# power.net
KiCad netlist of a schematic drawn in Altium Designer
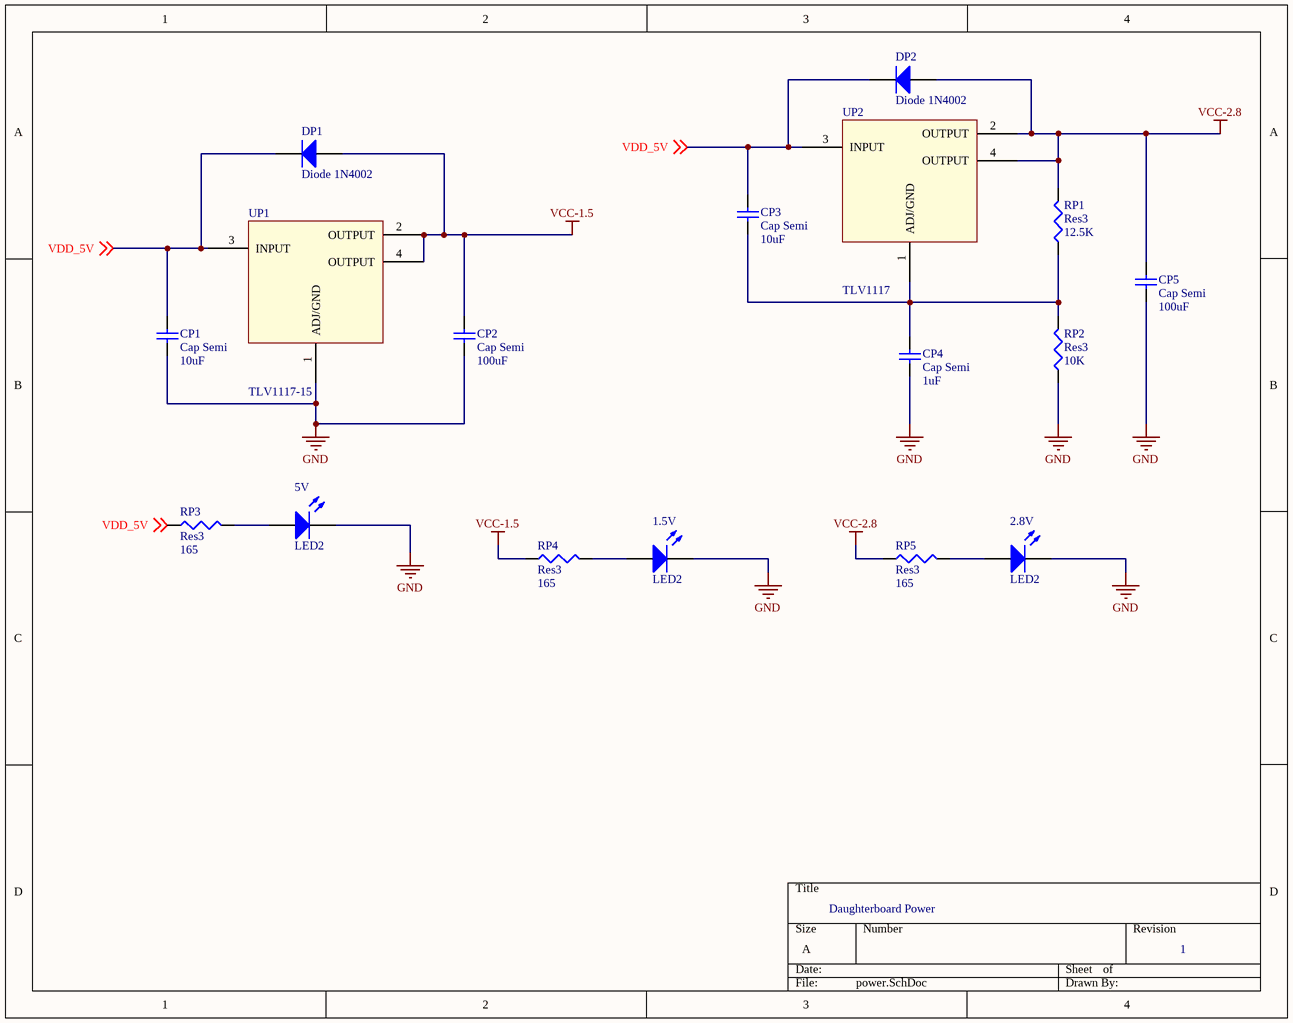
[diagram p0: power.SchDoc]

(export (version "E")
  (design (tool "Eeschema 10.0.6"))
  (components
    (comp (ref "1.5V")
      (value "LED2")
      (footprint "DIODE1608")
      (description "Typical RED, GREEN, YELLOW, AMBER GaAs LED")
      (fields (field (name "PUBLISHER") "Altium Limited"))
      (libsource (lib "Miscellaneous Devices") (part "LED2"))
    )
    (comp (ref "2.8V")
      (value "LED2")
      (footprint "DIODE1608")
      (description "Typical RED, GREEN, YELLOW, AMBER GaAs LED")
      (fields (field (name "PUBLISHER") "Altium Limited"))
      (libsource (lib "Miscellaneous Devices") (part "LED2"))
    )
    (comp (ref "5V")
      (value "LED2")
      (footprint "DIODE1608")
      (description "Typical RED, GREEN, YELLOW, AMBER GaAs LED")
      (fields (field (name "PUBLISHER") "Altium Limited"))
      (libsource (lib "Miscellaneous Devices") (part "LED2"))
    )
    (comp (ref "CP1")
      (value "Cap Semi")
      (footprint "CAPC1608L")
      (description "Capacitor (Semiconductor SIM Model)")
      (fields (field (name "ALTIUM_VALUE") "10uF") (field (name "PUBLISHER") "Altium Limited"))
      (libsource (lib "Miscellaneous Devices") (part "Cap Semi"))
    )
    (comp (ref "CP2")
      (value "Cap Semi")
      (footprint "CAPC1608L")
      (description "Capacitor (Semiconductor SIM Model)")
      (fields (field (name "ALTIUM_VALUE") "100uF") (field (name "PUBLISHER") "Altium Limited"))
      (libsource (lib "Miscellaneous Devices") (part "Cap Semi"))
    )
    (comp (ref "CP3")
      (value "Cap Semi")
      (footprint "CAPC1608L")
      (description "Capacitor (Semiconductor SIM Model)")
      (fields (field (name "ALTIUM_VALUE") "10uF") (field (name "PUBLISHER") "Altium Limited"))
      (libsource (lib "Miscellaneous Devices") (part "Cap Semi"))
    )
    (comp (ref "CP4")
      (value "Cap Semi")
      (footprint "CAPC1608L")
      (description "Capacitor (Semiconductor SIM Model)")
      (fields (field (name "ALTIUM_VALUE") "1uF") (field (name "PUBLISHER") "Altium Limited"))
      (libsource (lib "Miscellaneous Devices") (part "Cap Semi"))
    )
    (comp (ref "CP5")
      (value "Cap Semi")
      (footprint "CAPC1608L")
      (description "Capacitor (Semiconductor SIM Model)")
      (fields (field (name "ALTIUM_VALUE") "100uF") (field (name "PUBLISHER") "Altium Limited"))
      (libsource (lib "Miscellaneous Devices") (part "Cap Semi"))
    )
    (comp (ref "DP1")
      (value "Diode 1N4002")
      (footprint "DIO10.46-5.3x2.8")
      (description "1 Amp General Purpose Rectifier")
      (fields (field (name "PUBLISHER") "Altium Limited"))
      (libsource (lib "Miscellaneous Devices") (part "Diode 1N4002"))
    )
    (comp (ref "DP2")
      (value "Diode 1N4002")
      (footprint "DIO10.46-5.3x2.8")
      (description "1 Amp General Purpose Rectifier")
      (fields (field (name "PUBLISHER") "Altium Limited"))
      (libsource (lib "Miscellaneous Devices") (part "Diode 1N4002"))
    )
    (comp (ref "RP1")
      (value "Res3")
      (footprint "RESC1608L")
      (description "Resistor")
      (fields (field (name "ALTIUM_VALUE") "12.5K") (field (name "PUBLISHER") "Altium Limited"))
      (libsource (lib "Miscellaneous Devices") (part "Res3"))
    )
    (comp (ref "RP2")
      (value "Res3")
      (footprint "RESC1608L")
      (description "Resistor")
      (fields (field (name "ALTIUM_VALUE") "10K") (field (name "PUBLISHER") "Altium Limited"))
      (libsource (lib "Miscellaneous Devices") (part "Res3"))
    )
    (comp (ref "RP3")
      (value "Res3")
      (footprint "RESC1608L")
      (description "Resistor")
      (fields (field (name "ALTIUM_VALUE") "165") (field (name "PUBLISHER") "Altium Limited"))
      (libsource (lib "Miscellaneous Devices") (part "Res3"))
    )
    (comp (ref "RP4")
      (value "Res3")
      (footprint "RESC1608L")
      (description "Resistor")
      (fields (field (name "ALTIUM_VALUE") "165") (field (name "PUBLISHER") "Altium Limited"))
      (libsource (lib "Miscellaneous Devices") (part "Res3"))
    )
    (comp (ref "RP5")
      (value "Res3")
      (footprint "RESC1608L")
      (description "Resistor")
      (fields (field (name "ALTIUM_VALUE") "165") (field (name "PUBLISHER") "Altium Limited"))
      (libsource (lib "Miscellaneous Devices") (part "Res3"))
    )
    (comp (ref "UP1")
      (value "TLV1117-15")
      (footprint "TLV1117-DCY")
      (libsource (lib "daughterboard") (part "TLV1117"))
    )
    (comp (ref "UP2")
      (value "TLV1117")
      (footprint "TLV1117-DCY")
      (libsource (lib "daughterboard") (part "TLV1117"))
    )
  )
  (nets
    (net (code "1") (name "GND") (class "Default")
      (node (ref "1.5V") (pin "2") (pinfunction "K_2") (pintype "passive"))
      (node (ref "2.8V") (pin "2") (pinfunction "K_2") (pintype "passive"))
      (node (ref "5V") (pin "2") (pinfunction "K_2") (pintype "passive"))
      (node (ref "CP1") (pin "1") (pinfunction "1_1") (pintype "passive"))
      (node (ref "CP2") (pin "1") (pinfunction "1_1") (pintype "passive"))
      (node (ref "CP4") (pin "1") (pinfunction "1_1") (pintype "passive"))
      (node (ref "CP5") (pin "1") (pinfunction "1_1") (pintype "passive"))
      (node (ref "RP2") (pin "1") (pinfunction "1_1") (pintype "passive"))
      (node (ref "UP1") (pin "1") (pinfunction "ADJ/GND_1") (pintype "passive"))
    )
    (net (code "2") (name "Net-(1.5V-A)") (class "Default")
      (node (ref "1.5V") (pin "1") (pinfunction "A_1") (pintype "passive"))
      (node (ref "RP4") (pin "2") (pinfunction "2_2") (pintype "passive"))
    )
    (net (code "3") (name "Net-(2.8V-A)") (class "Default")
      (node (ref "2.8V") (pin "1") (pinfunction "A_1") (pintype "passive"))
      (node (ref "RP5") (pin "2") (pinfunction "2_2") (pintype "passive"))
    )
    (net (code "4") (name "Net-(5V-A)") (class "Default")
      (node (ref "5V") (pin "1") (pinfunction "A_1") (pintype "passive"))
      (node (ref "RP3") (pin "2") (pinfunction "2_2") (pintype "passive"))
    )
    (net (code "5") (name "Net-(UP2-ADJ{slash}GND)") (class "Default")
      (node (ref "CP3") (pin "1") (pinfunction "1_1") (pintype "passive"))
      (node (ref "CP4") (pin "2") (pinfunction "2_2") (pintype "passive"))
      (node (ref "RP1") (pin "1") (pinfunction "1_1") (pintype "passive"))
      (node (ref "RP2") (pin "2") (pinfunction "2_2") (pintype "passive"))
      (node (ref "UP2") (pin "1") (pinfunction "ADJ/GND_1") (pintype "passive"))
    )
    (net (code "6") (name "VCC-1.5") (class "Default")
      (node (ref "CP2") (pin "2") (pinfunction "2_2") (pintype "passive"))
      (node (ref "DP1") (pin "1") (pinfunction "A_1") (pintype "passive"))
      (node (ref "RP4") (pin "1") (pinfunction "1_1") (pintype "passive"))
      (node (ref "UP1") (pin "2") (pinfunction "OUTPUT_2") (pintype "passive"))
      (node (ref "UP1") (pin "4") (pinfunction "OUTPUT_4") (pintype "passive"))
    )
    (net (code "7") (name "VCC-2.8") (class "Default")
      (node (ref "CP5") (pin "2") (pinfunction "2_2") (pintype "passive"))
      (node (ref "DP2") (pin "1") (pinfunction "A_1") (pintype "passive"))
      (node (ref "RP1") (pin "2") (pinfunction "2_2") (pintype "passive"))
      (node (ref "RP5") (pin "1") (pinfunction "1_1") (pintype "passive"))
      (node (ref "UP2") (pin "2") (pinfunction "OUTPUT_2") (pintype "passive"))
      (node (ref "UP2") (pin "4") (pinfunction "OUTPUT_4") (pintype "passive"))
    )
    (net (code "8") (name "VDD_5V") (class "Default")
      (node (ref "CP1") (pin "2") (pinfunction "2_2") (pintype "passive"))
      (node (ref "CP3") (pin "2") (pinfunction "2_2") (pintype "passive"))
      (node (ref "DP1") (pin "2") (pinfunction "K_2") (pintype "passive"))
      (node (ref "DP2") (pin "2") (pinfunction "K_2") (pintype "passive"))
      (node (ref "RP3") (pin "1") (pinfunction "1_1") (pintype "passive"))
      (node (ref "UP1") (pin "3") (pinfunction "INPUT_3") (pintype "passive"))
      (node (ref "UP2") (pin "3") (pinfunction "INPUT_3") (pintype "passive"))
    )
  )
)
